# procesor.net
KiCad netlist of a schematic drawn in EAGLE
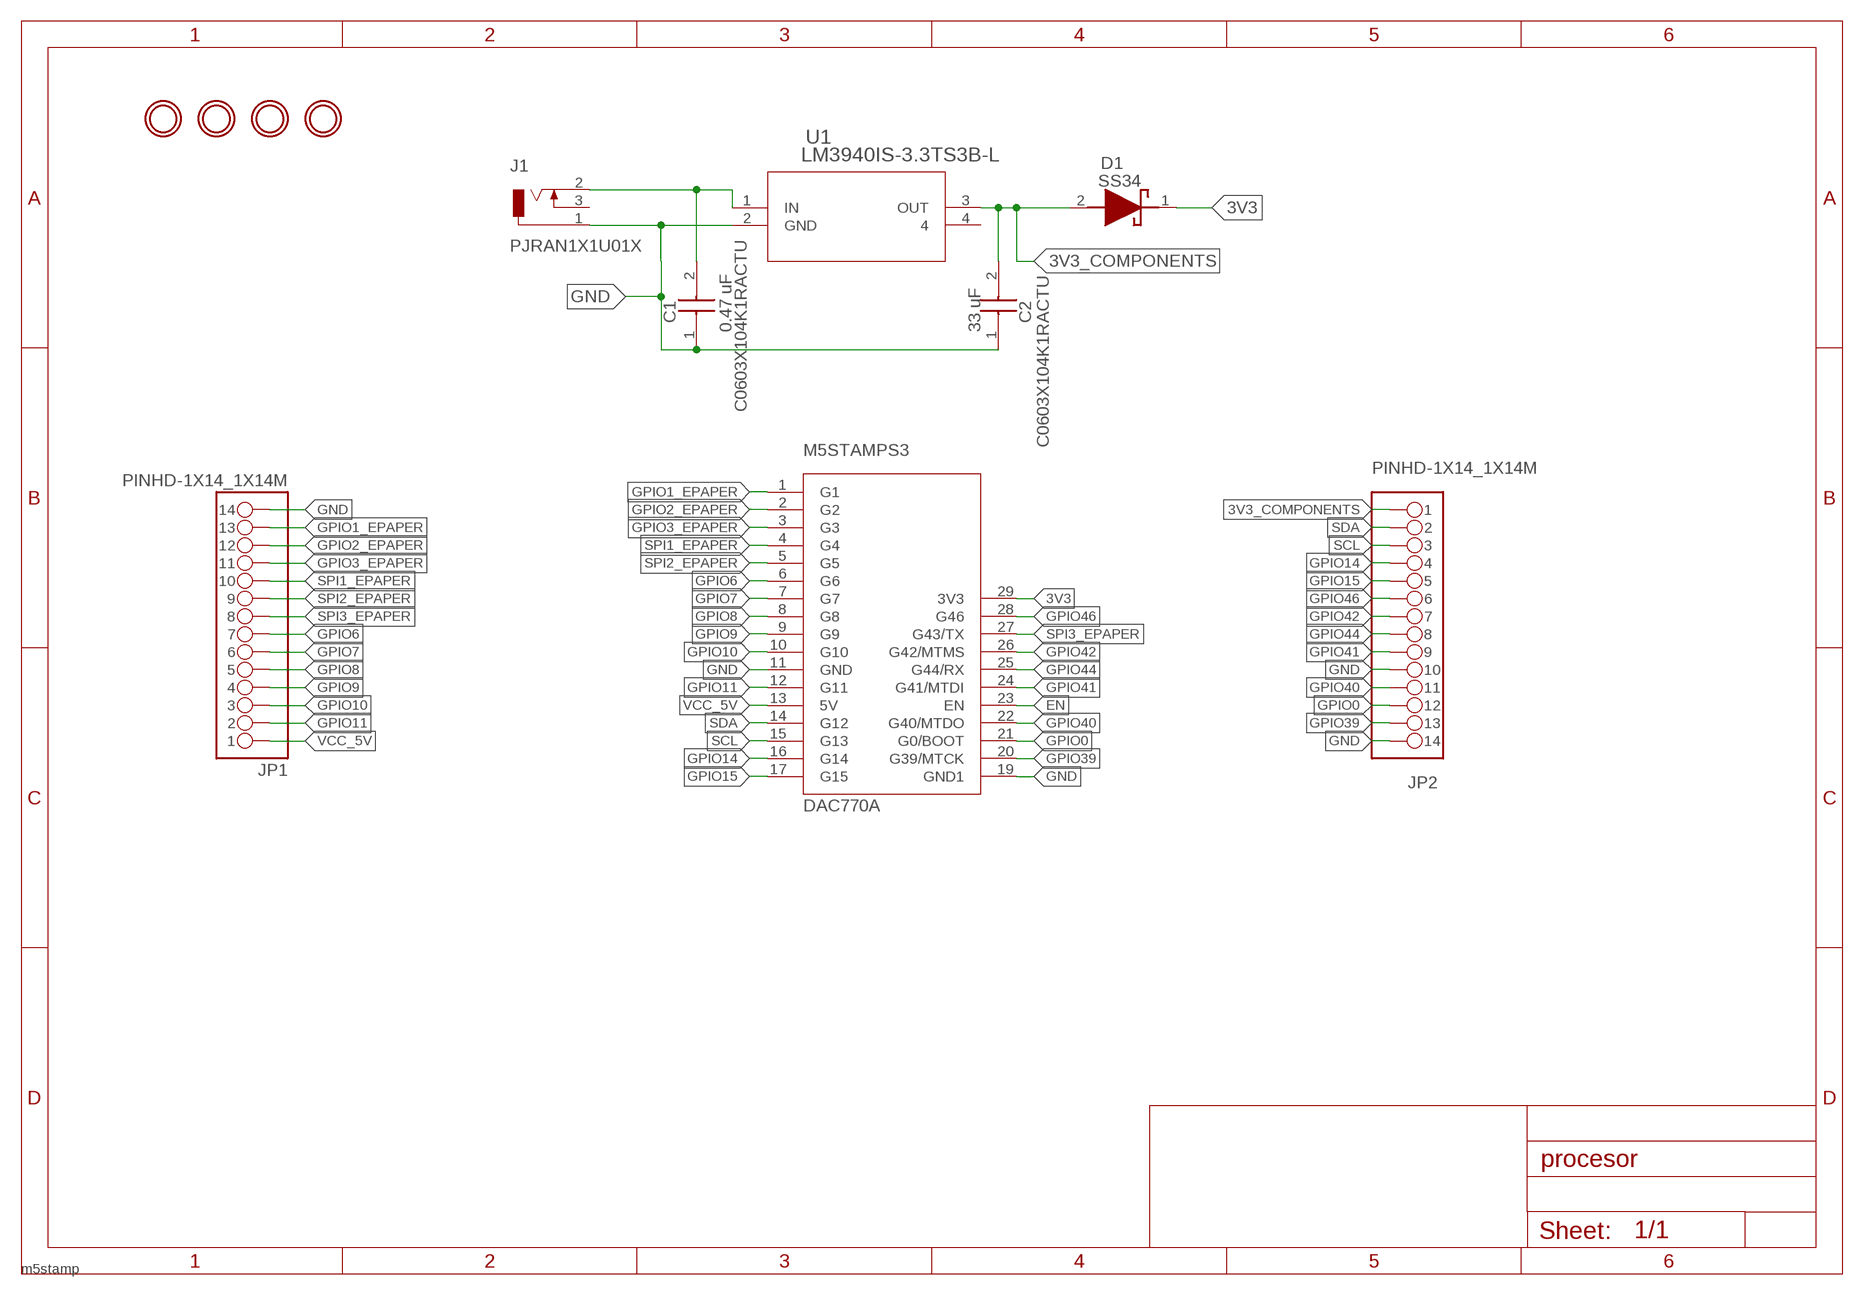
[diagram p0: schematic, sheet 1]

(export (version "E")
  (design (tool "Eeschema 10.0.6"))
  (components
    (comp (ref "C1")
      (value "C0603X104K1RACTU")
      (footprint "eagle-import:CAPC1608X100N")
      (description "0.47 uF")
      (fields (field (name "MOUSER_PART_NUMBER") "80-C0603X104K1RACTU"))
      (libsource (lib "eagle-import") (part "C0603X104K1RACTU"))
    )
    (comp (ref "C2")
      (value "C0603X104K1RACTU")
      (footprint "eagle-import:CAPC1608X100N")
      (description "33 uF")
      (fields (field (name "MOUSER_PART_NUMBER") "80-C0603X104K1RACTU"))
      (libsource (lib "eagle-import") (part "C0603X104K1RACTU"))
    )
    (comp (ref "D1")
      (value "SS34")
      (footprint "eagle-import:DIOM8059X256N")
      (fields (field (name "MOUSER_PART_NUMBER") "512-SS34"))
      (libsource (lib "eagle-import") (part "SS34"))
    )
    (comp (ref "J1")
      (value "PJRAN1X1U01X")
      (footprint "eagle-import:PJRAN1X1U01X")
      (fields (field (name "MANUFACTURER") "Switchcraft Inc. ") (field (name "MPN") "PJRAN1X1U01X "))
      (libsource (lib "eagle-import") (part "PJRAN1X1U01X"))
    )
    (comp (ref "JP1")
      (value "PINHD-1X14_1X14M")
      (footprint "eagle-import:1X14")
      (libsource (lib "eagle-import") (part "PINHD-1X14_1X14M"))
    )
    (comp (ref "JP2")
      (value "PINHD-1X14_1X14M")
      (footprint "eagle-import:1X14")
      (libsource (lib "eagle-import") (part "PINHD-1X14_1X14M"))
    )
    (comp (ref "M5STAMPS3")
      (value "DAC770A")
      (footprint "eagle-import:QFN127P2400X1800X470-36N")
      (libsource (lib "eagle-import") (part "DAC770A"))
    )
    (comp (ref "U$1")
      (value "MOUNTINGHOLE2.5")
      (footprint "eagle-import:MOUNTINGHOLE_2.5_PLATED")
      (libsource (lib "eagle-import") (part "MOUNTINGHOLE2.5"))
    )
    (comp (ref "U$3")
      (value "MOUNTINGHOLE2.5")
      (footprint "eagle-import:MOUNTINGHOLE_2.5_PLATED")
      (libsource (lib "eagle-import") (part "MOUNTINGHOLE2.5"))
    )
    (comp (ref "U$5")
      (value "MOUNTINGHOLE2.5")
      (footprint "eagle-import:MOUNTINGHOLE_2.5_PLATED")
      (libsource (lib "eagle-import") (part "MOUNTINGHOLE2.5"))
    )
    (comp (ref "U$6")
      (value "MOUNTINGHOLE2.5")
      (footprint "eagle-import:MOUNTINGHOLE_2.5_PLATED")
      (libsource (lib "eagle-import") (part "MOUNTINGHOLE2.5"))
    )
    (comp (ref "U1")
      (value "LM3940IS-3.3TS3B-L")
      (footprint "eagle-import:TS3B-L")
      (fields
        (field (name "MANUFACTURER_PART_NUMBER") "LM3940IS-3.3")
        (field (name "COPYRIGHT") "Copyright (C) 2024 Ultra Librarian. All rights reserved.")
      )
      (libsource (lib "eagle-import") (part "LM3940IS-3.3TS3B-L"))
    )
  )
  (nets
    (net (code "1") (name "3V3") (class "Default")
      (node (ref "D1") (pin "1") (pinfunction "K_1") (pintype "bidirectional"))
      (node (ref "M5STAMPS3") (pin "29") (pinfunction "3V3_29") (pintype "output"))
    )
    (net (code "2") (name "3V3_COMPONENTS") (class "Default")
      (node (ref "C2") (pin "2") (pinfunction "2_2") (pintype "bidirectional"))
      (node (ref "D1") (pin "2") (pinfunction "A_2") (pintype "bidirectional"))
      (node (ref "JP2") (pin "1") (pinfunction "1_1") (pintype "bidirectional"))
      (node (ref "U1") (pin "3") (pinfunction "OUT_3") (pintype "output"))
    )
    (net (code "3") (name "EN") (class "Default")
      (node (ref "M5STAMPS3") (pin "23") (pinfunction "EN_23") (pintype "input"))
    )
    (net (code "4") (name "GND") (class "Default")
      (node (ref "C1") (pin "1") (pinfunction "1_1") (pintype "bidirectional"))
      (node (ref "C2") (pin "1") (pinfunction "1_1") (pintype "bidirectional"))
      (node (ref "J1") (pin "1") (pinfunction "1_1") (pintype "passive"))
      (node (ref "JP1") (pin "14") (pinfunction "14_14") (pintype "bidirectional"))
      (node (ref "JP2") (pin "10") (pinfunction "10_10") (pintype "bidirectional"))
      (node (ref "JP2") (pin "14") (pinfunction "14_14") (pintype "bidirectional"))
      (node (ref "M5STAMPS3") (pin "11") (pinfunction "GND_11") (pintype "bidirectional"))
      (node (ref "M5STAMPS3") (pin "19") (pinfunction "GND1_19") (pintype "bidirectional"))
      (node (ref "U1") (pin "2") (pinfunction "GND_2") (pintype "passive"))
    )
    (net (code "5") (name "GPIO0") (class "Default")
      (node (ref "JP2") (pin "12") (pinfunction "12_12") (pintype "bidirectional"))
      (node (ref "M5STAMPS3") (pin "21") (pinfunction "G0/BOOT_21") (pintype "bidirectional"))
    )
    (net (code "6") (name "GPIO1_EPAPER") (class "Default")
      (node (ref "JP1") (pin "13") (pinfunction "13_13") (pintype "bidirectional"))
      (node (ref "M5STAMPS3") (pin "1") (pinfunction "G1_1") (pintype "bidirectional"))
    )
    (net (code "7") (name "GPIO2_EPAPER") (class "Default")
      (node (ref "JP1") (pin "12") (pinfunction "12_12") (pintype "bidirectional"))
      (node (ref "M5STAMPS3") (pin "2") (pinfunction "G2_2") (pintype "bidirectional"))
    )
    (net (code "8") (name "GPIO3_EPAPER") (class "Default")
      (node (ref "JP1") (pin "11") (pinfunction "11_11") (pintype "bidirectional"))
      (node (ref "M5STAMPS3") (pin "3") (pinfunction "G3_3") (pintype "bidirectional"))
    )
    (net (code "9") (name "GPIO6") (class "Default")
      (node (ref "JP1") (pin "7") (pinfunction "7_7") (pintype "bidirectional"))
      (node (ref "M5STAMPS3") (pin "6") (pinfunction "G6_6") (pintype "bidirectional"))
    )
    (net (code "10") (name "GPIO7") (class "Default")
      (node (ref "JP1") (pin "6") (pinfunction "6_6") (pintype "bidirectional"))
      (node (ref "M5STAMPS3") (pin "7") (pinfunction "G7_7") (pintype "bidirectional"))
    )
    (net (code "11") (name "GPIO8") (class "Default")
      (node (ref "JP1") (pin "5") (pinfunction "5_5") (pintype "bidirectional"))
      (node (ref "M5STAMPS3") (pin "8") (pinfunction "G8_8") (pintype "bidirectional"))
    )
    (net (code "12") (name "GPIO9") (class "Default")
      (node (ref "JP1") (pin "4") (pinfunction "4_4") (pintype "bidirectional"))
      (node (ref "M5STAMPS3") (pin "9") (pinfunction "G9_9") (pintype "bidirectional"))
    )
    (net (code "13") (name "GPIO10") (class "Default")
      (node (ref "JP1") (pin "3") (pinfunction "3_3") (pintype "bidirectional"))
      (node (ref "M5STAMPS3") (pin "10") (pinfunction "G10_10") (pintype "bidirectional"))
    )
    (net (code "14") (name "GPIO11") (class "Default")
      (node (ref "JP1") (pin "2") (pinfunction "2_2") (pintype "bidirectional"))
      (node (ref "M5STAMPS3") (pin "12") (pinfunction "G11_12") (pintype "bidirectional"))
    )
    (net (code "15") (name "GPIO14") (class "Default")
      (node (ref "JP2") (pin "4") (pinfunction "4_4") (pintype "bidirectional"))
      (node (ref "M5STAMPS3") (pin "16") (pinfunction "G14_16") (pintype "bidirectional"))
    )
    (net (code "16") (name "GPIO15") (class "Default")
      (node (ref "JP2") (pin "5") (pinfunction "5_5") (pintype "bidirectional"))
      (node (ref "M5STAMPS3") (pin "17") (pinfunction "G15_17") (pintype "bidirectional"))
    )
    (net (code "17") (name "GPIO39") (class "Default")
      (node (ref "JP2") (pin "13") (pinfunction "13_13") (pintype "bidirectional"))
      (node (ref "M5STAMPS3") (pin "20") (pinfunction "G39/MTCK_20") (pintype "bidirectional"))
    )
    (net (code "18") (name "GPIO40") (class "Default")
      (node (ref "JP2") (pin "11") (pinfunction "11_11") (pintype "bidirectional"))
      (node (ref "M5STAMPS3") (pin "22") (pinfunction "G40/MTDO_22") (pintype "bidirectional"))
    )
    (net (code "19") (name "GPIO41") (class "Default")
      (node (ref "JP2") (pin "9") (pinfunction "9_9") (pintype "bidirectional"))
      (node (ref "M5STAMPS3") (pin "24") (pinfunction "G41/MTDI_24") (pintype "bidirectional"))
    )
    (net (code "20") (name "GPIO42") (class "Default")
      (node (ref "JP2") (pin "7") (pinfunction "7_7") (pintype "bidirectional"))
      (node (ref "M5STAMPS3") (pin "26") (pinfunction "G42/MTMS_26") (pintype "bidirectional"))
    )
    (net (code "21") (name "GPIO44") (class "Default")
      (node (ref "JP2") (pin "8") (pinfunction "8_8") (pintype "bidirectional"))
      (node (ref "M5STAMPS3") (pin "25") (pinfunction "G44/RX_25") (pintype "bidirectional"))
    )
    (net (code "22") (name "GPIO46") (class "Default")
      (node (ref "JP2") (pin "6") (pinfunction "6_6") (pintype "bidirectional"))
      (node (ref "M5STAMPS3") (pin "28") (pinfunction "G46_28") (pintype "bidirectional"))
    )
    (net (code "23") (name "Net-(U1-IN)") (class "Default")
      (node (ref "C1") (pin "2") (pinfunction "2_2") (pintype "bidirectional"))
      (node (ref "J1") (pin "2") (pinfunction "2_2") (pintype "passive"))
      (node (ref "U1") (pin "1") (pinfunction "IN_1") (pintype "input"))
    )
    (net (code "24") (name "SCL") (class "Default")
      (node (ref "JP2") (pin "3") (pinfunction "3_3") (pintype "bidirectional"))
      (node (ref "M5STAMPS3") (pin "15") (pinfunction "G13_15") (pintype "bidirectional"))
    )
    (net (code "25") (name "SDA") (class "Default")
      (node (ref "JP2") (pin "2") (pinfunction "2_2") (pintype "bidirectional"))
      (node (ref "M5STAMPS3") (pin "14") (pinfunction "G12_14") (pintype "bidirectional"))
    )
    (net (code "26") (name "SPI1_EPAPER") (class "Default")
      (node (ref "JP1") (pin "10") (pinfunction "10_10") (pintype "bidirectional"))
      (node (ref "M5STAMPS3") (pin "4") (pinfunction "G4_4") (pintype "bidirectional"))
    )
    (net (code "27") (name "SPI2_EPAPER") (class "Default")
      (node (ref "JP1") (pin "9") (pinfunction "9_9") (pintype "bidirectional"))
      (node (ref "M5STAMPS3") (pin "5") (pinfunction "G5_5") (pintype "bidirectional"))
    )
    (net (code "28") (name "SPI3_EPAPER") (class "Default")
      (node (ref "JP1") (pin "8") (pinfunction "8_8") (pintype "bidirectional"))
      (node (ref "M5STAMPS3") (pin "27") (pinfunction "G43/TX_27") (pintype "bidirectional"))
    )
    (net (code "29") (name "VCC_5V") (class "Default")
      (node (ref "JP1") (pin "1") (pinfunction "1_1") (pintype "bidirectional"))
      (node (ref "M5STAMPS3") (pin "13") (pinfunction "5V_13") (pintype "bidirectional"))
    )
    (net (code "30") (name "unconnected-(J1-Pad3)") (class "Default")
      (node (ref "J1") (pin "3") (pinfunction "3_3") (pintype "passive"))
    )
    (net (code "31") (name "unconnected-(U1-Pad4)") (class "Default")
      (node (ref "U1") (pin "4") (pinfunction "4_4") (pintype "passive"))
    )
  )
)
